# MCU103A_USB_and_Power.net
KiCad netlist of a schematic drawn in Altium Designer
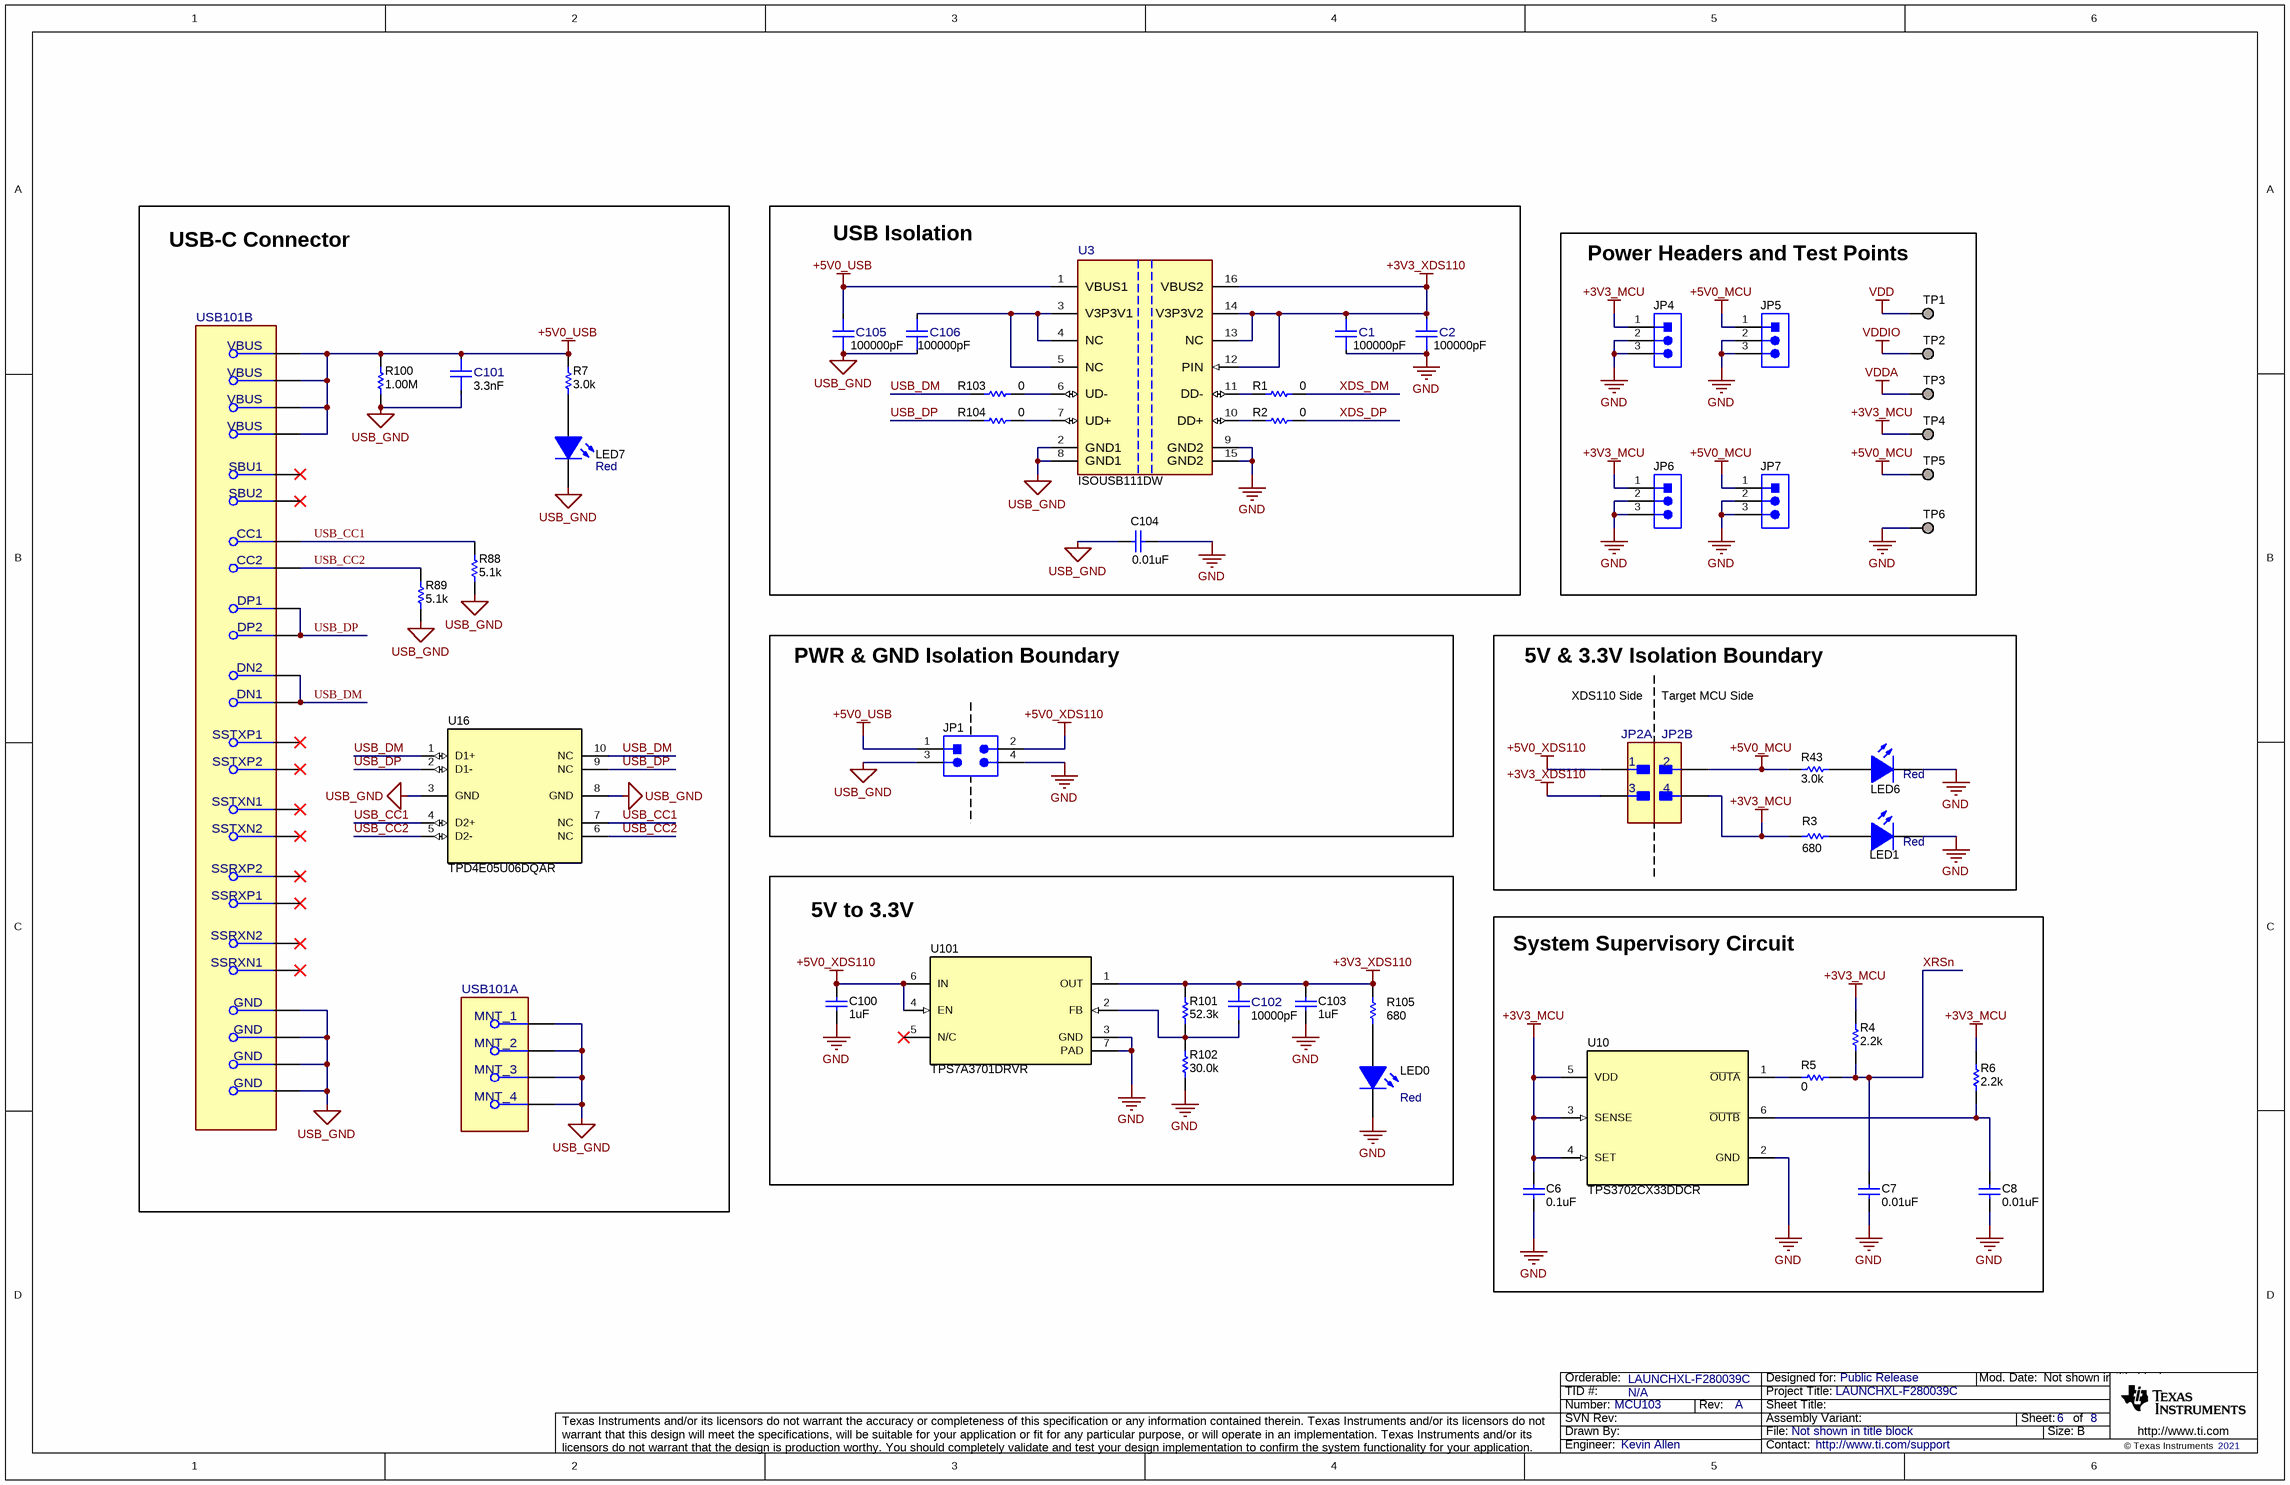
[diagram p0: MCU103A_USB_and_Power.SchDoc]

(export (version "E")
  (design (tool "Eeschema 10.0.6"))
  (components
    (comp (ref "C1")
      (value "885012205018")
      (footprint "FP-885012205018_0402-MFG")
      (description "0.1µF ±10% 10V Ceramic Capacitor X7R 0402 (1005 Metric)")
      (fields
        (field (name "MANUFACTURER") "Wurth Electronics")
        (field (name "MOUSER PART NUMBER") "710-885012205018")
        (field (name "VALUEDISPLAYED") "100000pF")
      )
      (libsource (lib "Altium Vault - TI") (part "SYM-885012205018"))
    )
    (comp (ref "C2")
      (value "885012205018")
      (footprint "FP-885012205018_0402-MFG")
      (description "0.1µF ±10% 10V Ceramic Capacitor X7R 0402 (1005 Metric)")
      (fields
        (field (name "MANUFACTURER") "Wurth Electronics")
        (field (name "MOUSER PART NUMBER") "710-885012205018")
        (field (name "VALUEDISPLAYED") "100000pF")
      )
      (libsource (lib "Altium Vault - TI") (part "SYM-885012205018"))
    )
    (comp (ref "C6")
      (value "GRM155R71A104KA01D")
      (footprint "0402")
      (description "CAP, CERM, 0.1 uF, 10 V, +/- 10%, X7R, 0402")
      (fields
        (field (name "VALUEDISPLAYED") "0.1uF")
        (field (name "MANUFACTURER") "MuRata")
        (field (name "PUBLISHER") "Texas Instruments")
      )
      (libsource (lib "Altium Vault - TI") (part "Capacitor"))
    )
    (comp (ref "C7")
      (value "GRM155R71E103KA01D")
      (footprint "0402")
      (description "CAP, CERM, 0.01 uF, 25 V, +/- 10%, X7R, 0402")
      (fields
        (field (name "VALUEDISPLAYED") "0.01uF")
        (field (name "MANUFACTURER") "MuRata")
        (field (name "PUBLISHER") "Texas Instruments")
      )
      (libsource (lib "Altium Vault - TI") (part "Capacitor"))
    )
    (comp (ref "C8")
      (value "GRM155R71E103KA01D")
      (footprint "0402")
      (description "CAP, CERM, 0.01 uF, 25 V, +/- 10%, X7R, 0402")
      (fields
        (field (name "VALUEDISPLAYED") "0.01uF")
        (field (name "MANUFACTURER") "MuRata")
        (field (name "PUBLISHER") "Texas Instruments")
      )
      (libsource (lib "Altium Vault - TI") (part "Capacitor"))
    )
    (comp (ref "C100")
      (value "885012105012")
      (footprint "0402")
      (description "CAP, CERM, 1 uF, 10 V,+/- 20%, X5R, 0402")
      (fields
        (field (name "VALUEDISPLAYED") "1uF")
        (field (name "MANUFACTURER") "Wurth Elektronik")
        (field (name "PUBLISHER") "Texas Instruments")
      )
      (libsource (lib "Altium Vault - TI") (part "Capacitor"))
    )
    (comp (ref "C101")
      (value "885012205064")
      (footprint "FP-885012205064_0402-MFG")
      (description "Cap Cer 3300pF 50V X7R 0402")
      (fields
        (field (name "MANUFACTURER") "Wurth Electronics")
        (field (name "DIGIKEY PART NUMBER") "732-7559-1-ND")
        (field (name "VALUEDISPLAYED") "3.3nF")
      )
      (libsource (lib "Altium Vault - TI") (part "SYM-885012205064"))
    )
    (comp (ref "C102")
      (value "885012205050")
      (footprint "FP-885012205050_0402-MFG")
      (description "10000pF ±10% 25V Ceramic Capacitor X7R 0402 (1005 Metric)")
      (fields
        (field (name "MANUFACTURER") "Wurth Electronics")
        (field (name "VALUEDISPLAYED") "10000pF")
        (field (name "MOUSER PART NUMBER") "710-885012205050")
      )
      (libsource (lib "Altium Vault - TI") (part "SYM-885012205050"))
    )
    (comp (ref "C103")
      (value "885012105012")
      (footprint "0402")
      (description "CAP, CERM, 1 uF, 10 V,+/- 20%, X5R, 0402")
      (fields
        (field (name "VALUEDISPLAYED") "1uF")
        (field (name "MANUFACTURER") "Wurth Elektronik")
        (field (name "PUBLISHER") "Texas Instruments")
      )
      (libsource (lib "Altium Vault - TI") (part "Capacitor"))
    )
    (comp (ref "C104")
      (value "1812SC103KAT1A")
      (footprint "1812")
      (description "CAP, CERM, 0.01 uF, 1500 V, +/- 10%, X7R, 1812")
      (fields
        (field (name "MANUFACTURER") "AVX")
        (field (name "VALUEDISPLAYED") "0.01uF")
        (field (name "PUBLISHER") "Texas Instruments")
      )
      (libsource (lib "Altium Vault - TI") (part "Capacitor"))
    )
    (comp (ref "C105")
      (value "885012205018")
      (footprint "FP-885012205018_0402-MFG")
      (description "0.1µF ±10% 10V Ceramic Capacitor X7R 0402 (1005 Metric)")
      (fields
        (field (name "MANUFACTURER") "Wurth Electronics")
        (field (name "MOUSER PART NUMBER") "710-885012205018")
        (field (name "VALUEDISPLAYED") "100000pF")
      )
      (libsource (lib "Altium Vault - TI") (part "SYM-885012205018"))
    )
    (comp (ref "C106")
      (value "885012205018")
      (footprint "FP-885012205018_0402-MFG")
      (description "0.1µF ±10% 10V Ceramic Capacitor X7R 0402 (1005 Metric)")
      (fields
        (field (name "MANUFACTURER") "Wurth Electronics")
        (field (name "MOUSER PART NUMBER") "710-885012205018")
        (field (name "VALUEDISPLAYED") "100000pF")
      )
      (libsource (lib "Altium Vault - TI") (part "SYM-885012205018"))
    )
    (comp (ref "JP1")
      (value "TSM-102-01-L-DV")
      (footprint "Samtec_TSM-102-01-x-DV")
      (description "Header, 2.54mm, 2x2, Gold, SMT")
      (fields (field (name "MANUFACTURER") "Samtec") (field (name "PUBLISHER") "Texas Instruments"))
      (libsource (lib "Altium Vault - TI") (part "Header_2x2"))
    )
    (comp (ref "JP2")
      (value "61300421121")
      (footprint "FP-61300421121_HDR4-MFG")
      (description "THT Vertical Pin Header WR-PHD, Pitch 2.54 mm, Dual Row, 4 pins")
      (fields
        (field (name "MANUFACTURER") "Wurth Electronics")
        (field (name "MOUSER PART NUMBER") "710-61300421121")
      )
      (libsource (lib "") (part "SYM-61300421121_1"))
    )
    (comp (ref "JP4")
      (value "61300311121")
      (footprint "WURTH_61300311121")
      (description "Header, 2.54 mm, 3x1, Gold, TH")
      (fields (field (name "MANUFACTURER") "Wurth Elektronik") (field (name "PUBLISHER") "Texas Instruments"))
      (libsource (lib "Altium Vault - TI") (part "Header_3x1"))
    )
    (comp (ref "JP5")
      (value "61300311121")
      (footprint "WURTH_61300311121")
      (description "Header, 2.54 mm, 3x1, Gold, TH")
      (fields (field (name "MANUFACTURER") "Wurth Elektronik") (field (name "PUBLISHER") "Texas Instruments"))
      (libsource (lib "Altium Vault - TI") (part "Header_3x1"))
    )
    (comp (ref "JP6")
      (value "61300311121")
      (footprint "WURTH_61300311121")
      (description "Header, 2.54 mm, 3x1, Gold, TH")
      (fields (field (name "MANUFACTURER") "Wurth Elektronik") (field (name "PUBLISHER") "Texas Instruments"))
      (libsource (lib "Altium Vault - TI") (part "Header_3x1"))
    )
    (comp (ref "JP7")
      (value "61300311121")
      (footprint "WURTH_61300311121")
      (description "Header, 2.54 mm, 3x1, Gold, TH")
      (fields (field (name "MANUFACTURER") "Wurth Elektronik") (field (name "PUBLISHER") "Texas Instruments"))
      (libsource (lib "Altium Vault - TI") (part "Header_3x1"))
    )
    (comp (ref "LED0")
      (value "Red")
      (footprint "WL-SMCW_RED_0805")
      (description "LED, Red, SMD")
      (fields (field (name "MANUFACTURER") "Wurth Elektronik") (field (name "PARTNUMBER") "150080SS75000"))
      (libsource (lib "Altium Vault - TI") (part "LED_A2_K1"))
    )
    (comp (ref "LED1")
      (value "Red")
      (footprint "WL-SMCW_RED_0805")
      (description "LED, Red, SMD")
      (fields (field (name "MANUFACTURER") "Wurth Elektronik") (field (name "PARTNUMBER") "150080SS75000"))
      (libsource (lib "Altium Vault - TI") (part "LED_A2_K1"))
    )
    (comp (ref "LED6")
      (value "Red")
      (footprint "WL-SMCW_RED_0805")
      (description "LED, Red, SMD")
      (fields (field (name "MANUFACTURER") "Wurth Elektronik") (field (name "PARTNUMBER") "150080SS75000"))
      (libsource (lib "Altium Vault - TI") (part "LED_A2_K1"))
    )
    (comp (ref "LED7")
      (value "Red")
      (footprint "WL-SMCW_RED_0805")
      (description "LED, Red, SMD")
      (fields (field (name "MANUFACTURER") "Wurth Elektronik") (field (name "PARTNUMBER") "150080SS75000"))
      (libsource (lib "Altium Vault - TI") (part "LED_A2_K1"))
    )
    (comp (ref "R1")
      (value "RC0402JR-070RL")
      (footprint "0402")
      (description "RES, 0, 5%, 0.063 W, 0402")
      (fields
        (field (name "MANUFACTURER") "Yageo America")
        (field (name "VALUEDISPLAYED") "0")
        (field (name "PUBLISHER") "Texas Instruments")
      )
      (libsource (lib "Altium Vault - TI") (part "Resistor"))
    )
    (comp (ref "R2")
      (value "RC0402JR-070RL")
      (footprint "0402")
      (description "RES, 0, 5%, 0.063 W, 0402")
      (fields
        (field (name "MANUFACTURER") "Yageo America")
        (field (name "VALUEDISPLAYED") "0")
        (field (name "PUBLISHER") "Texas Instruments")
      )
      (libsource (lib "Altium Vault - TI") (part "Resistor"))
    )
    (comp (ref "R3")
      (value "CRCW0402680RJNED")
      (footprint "0402")
      (description "RES, 680, 5%, 0.063 W, AEC-Q200 Grade 0, 0402")
      (fields (field (name "MANUFACTURER") "Vishay-Dale") (field (name "VALUEDISPLAYED") "680"))
      (libsource (lib "Altium Vault - TI") (part "Resistor"))
    )
    (comp (ref "R4")
      (value "CRCW04022K20JNED")
      (footprint "0402")
      (description "RES, 2.2 k, 5%, 0.063 W, AEC-Q200 Grade 0, 0402")
      (fields (field (name "VALUEDISPLAYED") "2.2k") (field (name "MANUFACTURER") "Vishay-Dale"))
      (libsource (lib "Altium Vault - TI") (part "Resistor"))
    )
    (comp (ref "R5")
      (value "CRCW04020000Z0ED")
      (footprint "0402")
      (description "RES, 0, 5%, 0.063 W, AEC-Q200 Grade 0, 0402")
      (fields (field (name "VALUEDISPLAYED") "0") (field (name "MANUFACTURER") "Vishay-Dale"))
      (libsource (lib "Altium Vault - TI") (part "Resistor"))
    )
    (comp (ref "R6")
      (value "CRCW06032K20JNEA")
      (footprint "0603")
      (description "RES, 2.2 k, 5%, 0.1 W, AEC-Q200 Grade 0, 0603")
      (fields (field (name "VALUEDISPLAYED") "2.2k") (field (name "MANUFACTURER") "Vishay-Dale"))
      (libsource (lib "Altium Vault - TI") (part "Resistor"))
    )
    (comp (ref "R7")
      (value "RC0603JR-073KL")
      (footprint "0603")
      (description "RES, 3.0 k, 5%, 0.1 W, 0603")
      (fields (field (name "MANUFACTURER") "Yageo") (field (name "VALUEDISPLAYED") "3.0k"))
      (libsource (lib "Altium Vault - TI") (part "Resistor"))
    )
    (comp (ref "R43")
      (value "RC0603JR-073KL")
      (footprint "0603")
      (description "RES, 3.0 k, 5%, 0.1 W, 0603")
      (fields (field (name "MANUFACTURER") "Yageo") (field (name "VALUEDISPLAYED") "3.0k"))
      (libsource (lib "Altium Vault - TI") (part "Resistor"))
    )
    (comp (ref "R88")
      (value "RC0603JR-075K1L")
      (footprint "0603")
      (description "RES, 5.1 k, 5%, 0.1 W, 0603")
      (fields (field (name "MANUFACTURER") "Yageo") (field (name "VALUEDISPLAYED") "5.1k"))
      (libsource (lib "Altium Vault - TI") (part "Resistor"))
    )
    (comp (ref "R89")
      (value "RC0603JR-075K1L")
      (footprint "0603")
      (description "RES, 5.1 k, 5%, 0.1 W, 0603")
      (fields (field (name "MANUFACTURER") "Yageo") (field (name "VALUEDISPLAYED") "5.1k"))
      (libsource (lib "Altium Vault - TI") (part "Resistor"))
    )
    (comp (ref "R100")
      (value "CRCW04021M00FKED")
      (footprint "0402")
      (description "RES, 1.00 M, 1%, 0.063 W, AEC-Q200 Grade 0, 0402")
      (fields (field (name "VALUEDISPLAYED") "1.00M") (field (name "MANUFACTURER") "Vishay-Dale"))
      (libsource (lib "Altium Vault - TI") (part "Resistor"))
    )
    (comp (ref "R101")
      (value "CRCW040252K3FKED")
      (footprint "0402")
      (description "RES, 52.3 k, 1%, 0.063 W, AEC-Q200 Grade 0, 0402")
      (fields (field (name "MANUFACTURER") "Vishay-Dale") (field (name "VALUEDISPLAYED") "52.3k"))
      (libsource (lib "Altium Vault - TI") (part "Resistor"))
    )
    (comp (ref "R102")
      (value "CRCW040230K0FKED")
      (footprint "0402")
      (description "RES, 30.0 k, 1%, 0.063 W, AEC-Q200 Grade 0, 0402")
      (fields (field (name "MANUFACTURER") "Vishay-Dale") (field (name "VALUEDISPLAYED") "30.0k"))
      (libsource (lib "Altium Vault - TI") (part "Resistor"))
    )
    (comp (ref "R103")
      (value "RC0402JR-070RL")
      (footprint "0402")
      (description "RES, 0, 5%, 0.063 W, 0402")
      (fields
        (field (name "MANUFACTURER") "Yageo America")
        (field (name "VALUEDISPLAYED") "0")
        (field (name "PUBLISHER") "Texas Instruments")
      )
      (libsource (lib "Altium Vault - TI") (part "Resistor"))
    )
    (comp (ref "R104")
      (value "RC0402JR-070RL")
      (footprint "0402")
      (description "RES, 0, 5%, 0.063 W, 0402")
      (fields
        (field (name "MANUFACTURER") "Yageo America")
        (field (name "VALUEDISPLAYED") "0")
        (field (name "PUBLISHER") "Texas Instruments")
      )
      (libsource (lib "Altium Vault - TI") (part "Resistor"))
    )
    (comp (ref "R105")
      (value "CRCW0402680RJNED")
      (footprint "0402")
      (description "RES, 680, 5%, 0.063 W, AEC-Q200 Grade 0, 0402")
      (fields (field (name "MANUFACTURER") "Vishay-Dale") (field (name "VALUEDISPLAYED") "680"))
      (libsource (lib "Altium Vault - TI") (part "Resistor"))
    )
    (comp (ref "TP1")
      (value "TESTPOINT")
      (footprint "TP_50MIL-25MILHOLE")
      (description "TEST POINT.  No entry in BOM.")
      (libsource (lib "Altium Vault - TI") (part "TESTPOINT"))
    )
    (comp (ref "TP2")
      (value "TESTPOINT")
      (footprint "TP_50MIL-25MILHOLE")
      (description "TEST POINT.  No entry in BOM.")
      (libsource (lib "Altium Vault - TI") (part "TESTPOINT"))
    )
    (comp (ref "TP3")
      (value "TESTPOINT")
      (footprint "TP_50MIL-25MILHOLE")
      (description "TEST POINT.  No entry in BOM.")
      (libsource (lib "Altium Vault - TI") (part "TESTPOINT"))
    )
    (comp (ref "TP4")
      (value "TESTPOINT")
      (footprint "TP_50MIL-25MILHOLE")
      (description "TEST POINT.  No entry in BOM.")
      (libsource (lib "Altium Vault - TI") (part "TESTPOINT"))
    )
    (comp (ref "TP5")
      (value "TESTPOINT")
      (footprint "TP_50MIL-25MILHOLE")
      (description "TEST POINT.  No entry in BOM.")
      (libsource (lib "Altium Vault - TI") (part "TESTPOINT"))
    )
    (comp (ref "TP6")
      (value "TESTPOINT")
      (footprint "TP_50MIL-25MILHOLE")
      (description "TEST POINT.  No entry in BOM.")
      (libsource (lib "Altium Vault - TI") (part "TESTPOINT"))
    )
    (comp (ref "U3")
      (value "ISOUSB111DW")
      (footprint "DW0016B-MFG")
      (description "Full/Low Speed Isolated USB Repeater, SOIC16-Wide")
      (fields (field (name "MANUFACTURER") "Texas Instruments") (field (name "PARTNUMBER") "ISOUSB111DW"))
      (libsource (lib "Altium Vault - TI") (part "SYM-ISOUSB111DW"))
    )
    (comp (ref "U10")
      (value "TPS3702CX33DDCR")
      (footprint "DDC0006A_N")
      (description "High-Accuracy, Fixed-Threshold OV/UV Monitor, DDC0006A (SOT-23-T-6)")
      (fields
        (field (name "ALTERNATE PARTNUMBER") "TPS3702CX33DDCT")
        (field (name "MANUFACTURER") "Texas Instruments")
        (field (name "PUBLISHER") "Texas Instruments")
      )
      (libsource (lib "Altium Vault - TI") (part "TPS3702"))
    )
    (comp (ref "U16")
      (value "TPD4E05U06DQAR")
      (footprint "DQA0010A")
      (description "4-Channel Ultra-Low-Capacitance IEC ESD Protection Diode, DQA0010A (USON-10)")
      (fields (field (name "MANUFACTURER") "Texas Instruments") (field (name "PARTNUMBER") "TPD4E05U06DQAR"))
      (libsource (lib "Altium Vault - TI") (part "TPD4E05U06"))
    )
    (comp (ref "U101")
      (value "TPS7A3701DRVR")
      (footprint "DRV0006A")
      (description "1% High-Accuracy, 1-A, Low-Dropout Regulator with Reverse Current Protection, DRV0006A (WSON-6)")
      (fields
        (field (name "PARTNUMBER") "TPS7A3701DRVR")
        (field (name "MANUFACTURER") "Texas Instruments")
        (field (name "ALTERNATE PARTNUMBER") "TPS7A3701DRVT")
        (field (name "PUBLISHER") "Texas Instruments")
      )
      (libsource (lib "Altium Vault - TI") (part "TPS7A37xxDRV-ADJ"))
    )
    (comp (ref "USB101")
      (value "MUP-U22001")
      (footprint "FP-MUP-U22001_CONN_USB_8MM94_8MM0-MFG")
      (description "Connector, USB Type-C 24 pin Mid Mount dual row Receptacle Surface Mount")
      (fields (field (name "MANUFACTURER") "MUP"))
      (libsource (lib "Altium Vault - TI") (part "SYM-MUP-U22001"))
    )
  )
  (nets
    (net (code "1") (name "+3V3_MCU") (class "Default")
      (node (ref "C6") (pin "2") (pinfunction "2_2") (pintype "passive"))
      (node (ref "JP2") (pin "4") (pinfunction "4_4") (pintype "passive"))
      (node (ref "JP4") (pin "1") (pinfunction "1_1") (pintype "passive"))
      (node (ref "JP6") (pin "1") (pinfunction "1_1") (pintype "passive"))
      (node (ref "R3") (pin "2") (pinfunction "2_2") (pintype "passive"))
      (node (ref "R4") (pin "2") (pinfunction "2_2") (pintype "passive"))
      (node (ref "R6") (pin "2") (pinfunction "2_2") (pintype "passive"))
      (node (ref "TP4") (pin "1") (pintype "passive"))
      (node (ref "U10") (pin "3") (pinfunction "SENSE_3") (pintype "input"))
      (node (ref "U10") (pin "4") (pinfunction "SET_4") (pintype "input"))
      (node (ref "U10") (pin "5") (pinfunction "VDD_5") (pintype "power_in"))
    )
    (net (code "2") (name "+3V3_XDS110") (class "Default")
      (node (ref "C1") (pin "2") (pinfunction "2_2") (pintype "passive"))
      (node (ref "C102") (pin "2") (pinfunction "2_2") (pintype "passive"))
      (node (ref "C103") (pin "1") (pinfunction "1_1") (pintype "passive"))
      (node (ref "C2") (pin "2") (pinfunction "2_2") (pintype "passive"))
      (node (ref "JP2") (pin "3") (pinfunction "3_3") (pintype "passive"))
      (node (ref "R101") (pin "2") (pinfunction "2_2") (pintype "passive"))
      (node (ref "R105") (pin "2") (pinfunction "2_2") (pintype "passive"))
      (node (ref "U101") (pin "1") (pinfunction "OUT_1") (pintype "power_in"))
      (node (ref "U3") (pin "12") (pinfunction "PIN_12") (pintype "input"))
      (node (ref "U3") (pin "13") (pinfunction "NC_13") (pintype "passive"))
      (node (ref "U3") (pin "14") (pinfunction "V3P3V2_14") (pintype "power_in"))
      (node (ref "U3") (pin "16") (pinfunction "VBUS2_16") (pintype "power_in"))
    )
    (net (code "3") (name "+5V0_MCU") (class "Default")
      (node (ref "JP2") (pin "2") (pinfunction "2_2") (pintype "passive"))
      (node (ref "JP5") (pin "1") (pinfunction "1_1") (pintype "passive"))
      (node (ref "JP7") (pin "1") (pinfunction "1_1") (pintype "passive"))
      (node (ref "R43") (pin "2") (pinfunction "2_2") (pintype "passive"))
      (node (ref "TP5") (pin "1") (pintype "passive"))
    )
    (net (code "4") (name "+5V0_USB") (class "Default")
      (node (ref "C101") (pin "2") (pinfunction "2_2") (pintype "passive"))
      (node (ref "C105") (pin "2") (pinfunction "2_2") (pintype "passive"))
      (node (ref "JP1") (pin "1") (pinfunction "1_1") (pintype "passive"))
      (node (ref "R100") (pin "2") (pinfunction "2_2") (pintype "passive"))
      (node (ref "R7") (pin "2") (pinfunction "2_2") (pintype "passive"))
      (node (ref "U3") (pin "1") (pinfunction "VBUS1_1") (pintype "power_in"))
      (node (ref "USB101") (pin "A4") (pinfunction "VBUS_A4") (pintype "passive"))
      (node (ref "USB101") (pin "A9") (pinfunction "VBUS_A9") (pintype "passive"))
      (node (ref "USB101") (pin "B4") (pinfunction "VBUS_B4") (pintype "passive"))
      (node (ref "USB101") (pin "B9") (pinfunction "VBUS_B9") (pintype "passive"))
    )
    (net (code "5") (name "+5V0_XDS110") (class "Default")
      (node (ref "C100") (pin "1") (pinfunction "1_1") (pintype "passive"))
      (node (ref "JP1") (pin "2") (pinfunction "2_2") (pintype "passive"))
      (node (ref "JP2") (pin "1") (pinfunction "1_1") (pintype "passive"))
      (node (ref "U101") (pin "4") (pinfunction "EN_4") (pintype "input"))
      (node (ref "U101") (pin "6") (pinfunction "IN_6") (pintype "power_in"))
    )
    (net (code "6") (name "/USB_CC1") (class "Default")
      (node (ref "R88") (pin "2") (pinfunction "2_2") (pintype "passive"))
      (node (ref "U16") (pin "4") (pinfunction "D2+_4") (pintype "bidirectional"))
      (node (ref "U16") (pin "7") (pinfunction "NC_7") (pintype "passive"))
      (node (ref "USB101") (pin "A5") (pinfunction "CC1_A5") (pintype "passive"))
    )
    (net (code "7") (name "/USB_CC2") (class "Default")
      (node (ref "R89") (pin "2") (pinfunction "2_2") (pintype "passive"))
      (node (ref "U16") (pin "5") (pinfunction "D2-_5") (pintype "bidirectional"))
      (node (ref "U16") (pin "6") (pinfunction "NC_6") (pintype "passive"))
      (node (ref "USB101") (pin "B5") (pinfunction "CC2_B5") (pintype "passive"))
    )
    (net (code "8") (name "/USB_DM") (class "Default")
      (node (ref "R103") (pin "1") (pinfunction "1_1") (pintype "passive"))
      (node (ref "U16") (pin "1") (pinfunction "D1+_1") (pintype "bidirectional"))
      (node (ref "U16") (pin "10") (pinfunction "NC_10") (pintype "passive"))
      (node (ref "USB101") (pin "A7") (pinfunction "DN1_A7") (pintype "passive"))
      (node (ref "USB101") (pin "B7") (pinfunction "DN2_B7") (pintype "passive"))
    )
    (net (code "9") (name "/USB_DP") (class "Default")
      (node (ref "R104") (pin "1") (pinfunction "1_1") (pintype "passive"))
      (node (ref "U16") (pin "2") (pinfunction "D1-_2") (pintype "bidirectional"))
      (node (ref "U16") (pin "9") (pinfunction "NC_9") (pintype "passive"))
      (node (ref "USB101") (pin "A6") (pinfunction "DP1_A6") (pintype "passive"))
      (node (ref "USB101") (pin "B6") (pinfunction "DP2_B6") (pintype "passive"))
    )
    (net (code "10") (name "/XDS_DM") (class "Default")
      (node (ref "R1") (pin "2") (pinfunction "2_2") (pintype "passive"))
    )
    (net (code "11") (name "/XDS_DP") (class "Default")
      (node (ref "R2") (pin "2") (pinfunction "2_2") (pintype "passive"))
    )
    (net (code "12") (name "/XRSn") (class "Default")
      (node (ref "C7") (pin "1") (pinfunction "1_1") (pintype "passive"))
      (node (ref "R4") (pin "1") (pinfunction "1_1") (pintype "passive"))
      (node (ref "R5") (pin "2") (pinfunction "2_2") (pintype "passive"))
    )
    (net (code "13") (name "GND") (class "Default")
      (node (ref "C1") (pin "1") (pinfunction "1_1") (pintype "passive"))
      (node (ref "C100") (pin "2") (pinfunction "2_2") (pintype "passive"))
      (node (ref "C103") (pin "2") (pinfunction "2_2") (pintype "passive"))
      (node (ref "C104") (pin "1") (pinfunction "1_1") (pintype "passive"))
      (node (ref "C2") (pin "1") (pinfunction "1_1") (pintype "passive"))
      (node (ref "C6") (pin "1") (pinfunction "1_1") (pintype "passive"))
      (node (ref "C7") (pin "2") (pinfunction "2_2") (pintype "passive"))
      (node (ref "C8") (pin "2") (pinfunction "2_2") (pintype "passive"))
      (node (ref "JP1") (pin "4") (pinfunction "4_4") (pintype "passive"))
      (node (ref "JP4") (pin "2") (pinfunction "2_2") (pintype "passive"))
      (node (ref "JP4") (pin "3") (pinfunction "3_3") (pintype "passive"))
      (node (ref "JP5") (pin "2") (pinfunction "2_2") (pintype "passive"))
      (node (ref "JP5") (pin "3") (pinfunction "3_3") (pintype "passive"))
      (node (ref "JP6") (pin "2") (pinfunction "2_2") (pintype "passive"))
      (node (ref "JP6") (pin "3") (pinfunction "3_3") (pintype "passive"))
      (node (ref "JP7") (pin "2") (pinfunction "2_2") (pintype "passive"))
      (node (ref "JP7") (pin "3") (pinfunction "3_3") (pintype "passive"))
      (node (ref "LED0") (pin "1") (pinfunction "K_1") (pintype "passive"))
      (node (ref "LED1") (pin "1") (pinfunction "K_1") (pintype "passive"))
      (node (ref "LED6") (pin "1") (pinfunction "K_1") (pintype "passive"))
      (node (ref "R102") (pin "1") (pinfunction "1_1") (pintype "passive"))
      (node (ref "TP6") (pin "1") (pintype "passive"))
      (node (ref "U10") (pin "2") (pinfunction "GND_2") (pintype "power_in"))
      (node (ref "U101") (pin "3") (pinfunction "GND_3") (pintype "power_in"))
      (node (ref "U101") (pin "7") (pinfunction "PAD_7") (pintype "power_in"))
      (node (ref "U3") (pin "15") (pinfunction "GND2_15") (pintype "power_in"))
      (node (ref "U3") (pin "9") (pinfunction "GND2_9") (pintype "power_in"))
    )
    (net (code "14") (name "Net-(LED0-A)") (class "Default")
      (node (ref "LED0") (pin "2") (pinfunction "A_2") (pintype "passive"))
      (node (ref "R105") (pin "1") (pinfunction "1_1") (pintype "passive"))
    )
    (net (code "15") (name "Net-(LED1-A)") (class "Default")
      (node (ref "LED1") (pin "2") (pinfunction "A_2") (pintype "passive"))
      (node (ref "R3") (pin "1") (pinfunction "1_1") (pintype "passive"))
    )
    (net (code "16") (name "Net-(LED6-A)") (class "Default")
      (node (ref "LED6") (pin "2") (pinfunction "A_2") (pintype "passive"))
      (node (ref "R43") (pin "1") (pinfunction "1_1") (pintype "passive"))
    )
    (net (code "17") (name "Net-(LED7-A)") (class "Default")
      (node (ref "LED7") (pin "2") (pinfunction "A_2") (pintype "passive"))
      (node (ref "R7") (pin "1") (pinfunction "1_1") (pintype "passive"))
    )
    (net (code "18") (name "Net-(U3-DD+)") (class "Default")
      (node (ref "R2") (pin "1") (pinfunction "1_1") (pintype "passive"))
      (node (ref "U3") (pin "10") (pinfunction "DD+_10") (pintype "bidirectional"))
    )
    (net (code "19") (name "Net-(U3-DD-)") (class "Default")
      (node (ref "R1") (pin "1") (pinfunction "1_1") (pintype "passive"))
      (node (ref "U3") (pin "11") (pinfunction "DD-_11") (pintype "bidirectional"))
    )
    (net (code "20") (name "Net-(U3-UD+)") (class "Default")
      (node (ref "R104") (pin "2") (pinfunction "2_2") (pintype "passive"))
      (node (ref "U3") (pin "7") (pinfunction "UD+_7") (pintype "bidirectional"))
    )
    (net (code "21") (name "Net-(U3-UD-)") (class "Default")
      (node (ref "R103") (pin "2") (pinfunction "2_2") (pintype "passive"))
      (node (ref "U3") (pin "6") (pinfunction "UD-_6") (pintype "bidirectional"))
    )
    (net (code "22") (name "Net-(U3-V3P3V1)") (class "Default")
      (node (ref "C106") (pin "2") (pinfunction "2_2") (pintype "passive"))
      (node (ref "U3") (pin "3") (pinfunction "V3P3V1_3") (pintype "power_in"))
      (node (ref "U3") (pin "4") (pinfunction "NC_4") (pintype "passive"))
      (node (ref "U3") (pin "5") (pinfunction "NC_5") (pintype "passive"))
    )
    (net (code "23") (name "Net-(U10-OUTA)") (class "Default")
      (node (ref "R5") (pin "1") (pinfunction "1_1") (pintype "passive"))
      (node (ref "U10") (pin "1") (pinfunction "OUTA_1") (pintype "open_collector"))
    )
    (net (code "24") (name "Net-(U10-OUTB)") (class "Default")
      (node (ref "C8") (pin "1") (pinfunction "1_1") (pintype "passive"))
      (node (ref "R6") (pin "1") (pinfunction "1_1") (pintype "passive"))
      (node (ref "U10") (pin "6") (pinfunction "OUTB_6") (pintype "open_collector"))
    )
    (net (code "25") (name "Net-(U101-FB)") (class "Default")
      (node (ref "C102") (pin "1") (pinfunction "1_1") (pintype "passive"))
      (node (ref "R101") (pin "1") (pinfunction "1_1") (pintype "passive"))
      (node (ref "R102") (pin "2") (pinfunction "2_2") (pintype "passive"))
      (node (ref "U101") (pin "2") (pinfunction "FB_2") (pintype "input"))
    )
    (net (code "26") (name "USB_GND") (class "Default")
      (node (ref "C101") (pin "1") (pinfunction "1_1") (pintype "passive"))
      (node (ref "C104") (pin "2") (pinfunction "2_2") (pintype "passive"))
      (node (ref "C105") (pin "1") (pinfunction "1_1") (pintype "passive"))
      (node (ref "C106") (pin "1") (pinfunction "1_1") (pintype "passive"))
      (node (ref "JP1") (pin "3") (pinfunction "3_3") (pintype "passive"))
      (node (ref "LED7") (pin "1") (pinfunction "K_1") (pintype "passive"))
      (node (ref "R100") (pin "1") (pinfunction "1_1") (pintype "passive"))
      (node (ref "R88") (pin "1") (pinfunction "1_1") (pintype "passive"))
      (node (ref "R89") (pin "1") (pinfunction "1_1") (pintype "passive"))
      (node (ref "U16") (pin "3") (pinfunction "GND_3") (pintype "power_in"))
      (node (ref "U16") (pin "8") (pinfunction "GND_8") (pintype "power_in"))
      (node (ref "U3") (pin "2") (pinfunction "GND1_2") (pintype "power_in"))
      (node (ref "U3") (pin "8") (pinfunction "GND1_8") (pintype "power_in"))
      (node (ref "USB101") (pin "1") (pinfunction "MNT_1_1") (pintype "passive"))
      (node (ref "USB101") (pin "2") (pinfunction "MNT_2_2") (pintype "passive"))
      (node (ref "USB101") (pin "3") (pinfunction "MNT_3_3") (pintype "passive"))
      (node (ref "USB101") (pin "4") (pinfunction "MNT_4_4") (pintype "passive"))
      (node (ref "USB101") (pin "A1") (pinfunction "GND_A1") (pintype "passive"))
      (node (ref "USB101") (pin "A12") (pinfunction "GND_A12") (pintype "passive"))
      (node (ref "USB101") (pin "B1") (pinfunction "GND_B1") (pintype "passive"))
      (node (ref "USB101") (pin "B12") (pinfunction "GND_B12") (pintype "passive"))
    )
    (net (code "27") (name "VDD") (class "Default") (node (ref "TP1") (pin "1") (pintype "passive")))
    (net (code "28") (name "VDDA") (class "Default") (node (ref "TP3") (pin "1") (pintype "passive")))
    (net (code "29") (name "VDDIO") (class "Default") (node (ref "TP2") (pin "1") (pintype "passive")))
    (net (code "30") (name "unconnected-(U101-N{slash}C-Pad5)") (class "Default")
      (node (ref "U101") (pin "5") (pinfunction "N/C_5") (pintype "passive+no_connect"))
    )
    (net (code "31") (name "unconnected-(USB101B-SBU1-PadA8)") (class "Default")
      (node (ref "USB101") (pin "A8") (pinfunction "SBU1_A8") (pintype "passive+no_connect"))
    )
    (net (code "32") (name "unconnected-(USB101B-SBU2-PadB8)") (class "Default")
      (node (ref "USB101") (pin "B8") (pinfunction "SBU2_B8") (pintype "passive+no_connect"))
    )
    (net (code "33") (name "unconnected-(USB101B-SSRXN1-PadB10)") (class "Default")
      (node (ref "USB101") (pin "B10") (pinfunction "SSRXN1_B10") (pintype "passive+no_connect"))
    )
    (net (code "34") (name "unconnected-(USB101B-SSRXN2-PadA10)") (class "Default")
      (node (ref "USB101") (pin "A10") (pinfunction "SSRXN2_A10") (pintype "passive+no_connect"))
    )
    (net (code "35") (name "unconnected-(USB101B-SSRXP1-PadB11)") (class "Default")
      (node (ref "USB101") (pin "B11") (pinfunction "SSRXP1_B11") (pintype "passive+no_connect"))
    )
    (net (code "36") (name "unconnected-(USB101B-SSRXP2-PadA11)") (class "Default")
      (node (ref "USB101") (pin "A11") (pinfunction "SSRXP2_A11") (pintype "passive+no_connect"))
    )
    (net (code "37") (name "unconnected-(USB101B-SSTXN1-PadA3)") (class "Default")
      (node (ref "USB101") (pin "A3") (pinfunction "SSTXN1_A3") (pintype "passive+no_connect"))
    )
    (net (code "38") (name "unconnected-(USB101B-SSTXN2-PadB3)") (class "Default")
      (node (ref "USB101") (pin "B3") (pinfunction "SSTXN2_B3") (pintype "passive+no_connect"))
    )
    (net (code "39") (name "unconnected-(USB101B-SSTXP1-PadA2)") (class "Default")
      (node (ref "USB101") (pin "A2") (pinfunction "SSTXP1_A2") (pintype "passive+no_connect"))
    )
    (net (code "40") (name "unconnected-(USB101B-SSTXP2-PadB2)") (class "Default")
      (node (ref "USB101") (pin "B2") (pinfunction "SSTXP2_B2") (pintype "passive+no_connect"))
    )
  )
)
